# TemperatureSensor.net
KiCad netlist of a schematic drawn in Altium Designer
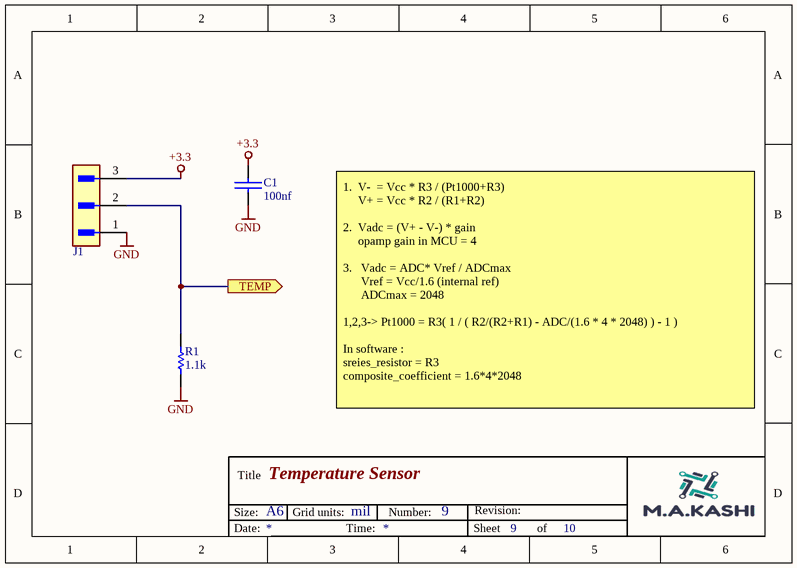
[diagram p0: TemperatureSensor.SchDoc]

(export (version "E")
  (design (tool "Eeschema 10.0.6"))
  (components
    (comp (ref "C1")
      (value "100nf")
      (footprint "cap_0805_A")
      (description "octopart or digikey description!")
      (fields (field (name "PART NUMBER") "C0402X7R160-104KNE"))
      (libsource (lib "E-component") (part "Capacitor"))
    )
    (comp (ref "J1")
      (value "Connector")
      (footprint "Phoenix 3 0D")
      (libsource (lib "E-component") (part "Connector 3 pin"))
    )
    (comp (ref "R1")
      (value "1.1k")
      (footprint "RES_0805_A")
      (description "octopart or digikey description!")
      (fields (field (name "PART NUMBER") "RC0402JR-07100RL"))
      (libsource (lib "E-component") (part "Resistor"))
    )
  )
  (nets
    (net (code "1") (name "+3.3") (class "Default")
      (node (ref "C1") (pin "2") (pinfunction "2_2") (pintype "passive"))
      (node (ref "J1") (pin "3") (pinfunction "3_3") (pintype "passive"))
    )
    (net (code "2") (name "/TEMP") (class "Default")
      (node (ref "J1") (pin "2") (pinfunction "2_2") (pintype "passive"))
      (node (ref "R1") (pin "2") (pinfunction "2_2") (pintype "passive"))
    )
    (net (code "3") (name "GND") (class "Default")
      (node (ref "C1") (pin "1") (pinfunction "1_1") (pintype "passive"))
      (node (ref "J1") (pin "1") (pinfunction "1_1") (pintype "passive"))
      (node (ref "R1") (pin "1") (pinfunction "1_1") (pintype "passive"))
    )
  )
)
